# Led_Bar.net
KiCad netlist of a schematic drawn in EAGLE
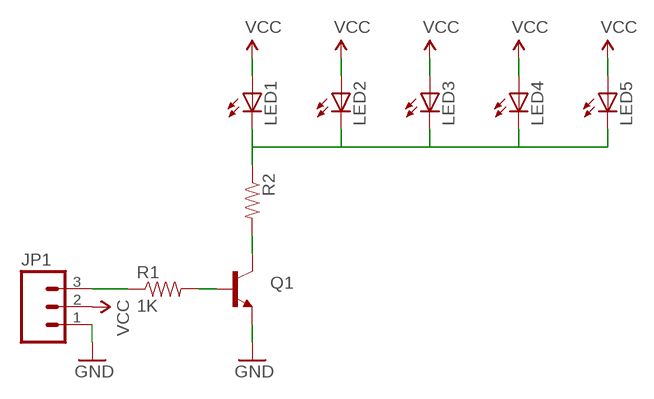
[diagram p0: schematic, sheet 1]

(export (version "E")
  (design (tool "Eeschema 10.0.6"))
  (components
    (comp (ref "JP1")
      (value "M03PTH")
      (footprint "eagle-import:1X03")
      (libsource (lib "eagle-import") (part "M03PTH"))
    )
    (comp (ref "LED1")
      (value "LED5MM")
      (footprint "eagle-import:LED5MM")
      (libsource (lib "eagle-import") (part "LED5MM"))
    )
    (comp (ref "LED2")
      (value "LED5MM")
      (footprint "eagle-import:LED5MM")
      (libsource (lib "eagle-import") (part "LED5MM"))
    )
    (comp (ref "LED3")
      (value "LED5MM")
      (footprint "eagle-import:LED5MM")
      (libsource (lib "eagle-import") (part "LED5MM"))
    )
    (comp (ref "LED4")
      (value "LED5MM")
      (footprint "eagle-import:LED5MM")
      (libsource (lib "eagle-import") (part "LED5MM"))
    )
    (comp (ref "LED5")
      (value "LED5MM")
      (footprint "eagle-import:LED5MM")
      (libsource (lib "eagle-import") (part "LED5MM"))
    )
    (comp (ref "Q1")
      (value "TRANSISTOR_NPNTO-92-AMMO")
      (footprint "eagle-import:TO-92-AMMO")
      (libsource (lib "eagle-import") (part "TRANSISTOR_NPNTO-92-AMMO"))
    )
    (comp (ref "R1")
      (value "1K")
      (footprint "eagle-import:AXIAL-0.3")
      (libsource (lib "eagle-import") (part "RESISTORAXIAL-0.3"))
    )
    (comp (ref "R2")
      (value "RESISTORAXIAL-0.3")
      (footprint "eagle-import:AXIAL-0.3")
      (libsource (lib "eagle-import") (part "RESISTORAXIAL-0.3"))
    )
  )
  (nets
    (net (code "1") (name "GND") (class "Default")
      (node (ref "JP1") (pin "1") (pinfunction "1_1") (pintype "passive"))
      (node (ref "Q1") (pin "1") (pinfunction "E_1") (pintype "passive"))
    )
    (net (code "2") (name "Net-(LED1-C)") (class "Default")
      (node (ref "LED1") (pin "K") (pinfunction "C_K") (pintype "passive"))
      (node (ref "LED2") (pin "K") (pinfunction "C_K") (pintype "passive"))
      (node (ref "LED3") (pin "K") (pinfunction "C_K") (pintype "passive"))
      (node (ref "LED4") (pin "K") (pinfunction "C_K") (pintype "passive"))
      (node (ref "LED5") (pin "K") (pinfunction "C_K") (pintype "passive"))
      (node (ref "R2") (pin "P$1") (pinfunction "1_P$1") (pintype "passive"))
    )
    (net (code "3") (name "Net-(Q1-B)") (class "Default")
      (node (ref "Q1") (pin "2") (pinfunction "B_2") (pintype "passive"))
      (node (ref "R1") (pin "P$2") (pinfunction "2_P$2") (pintype "passive"))
    )
    (net (code "4") (name "Net-(Q1-C)") (class "Default")
      (node (ref "Q1") (pin "3") (pinfunction "C_3") (pintype "passive"))
      (node (ref "R2") (pin "P$2") (pinfunction "2_P$2") (pintype "passive"))
    )
    (net (code "5") (name "Net-(R1-1)") (class "Default")
      (node (ref "JP1") (pin "3") (pinfunction "3_3") (pintype "passive"))
      (node (ref "R1") (pin "P$1") (pinfunction "1_P$1") (pintype "passive"))
    )
    (net (code "6") (name "VCC") (class "Default")
      (node (ref "JP1") (pin "2") (pinfunction "2_2") (pintype "passive"))
      (node (ref "LED1") (pin "A") (pinfunction "A_A") (pintype "passive"))
      (node (ref "LED2") (pin "A") (pinfunction "A_A") (pintype "passive"))
      (node (ref "LED3") (pin "A") (pinfunction "A_A") (pintype "passive"))
      (node (ref "LED4") (pin "A") (pinfunction "A_A") (pintype "passive"))
      (node (ref "LED5") (pin "A") (pinfunction "A_A") (pintype "passive"))
    )
  )
)
